# generator_cd4047_trafo_ct.net
KiCad netlist of a schematic drawn in EAGLE
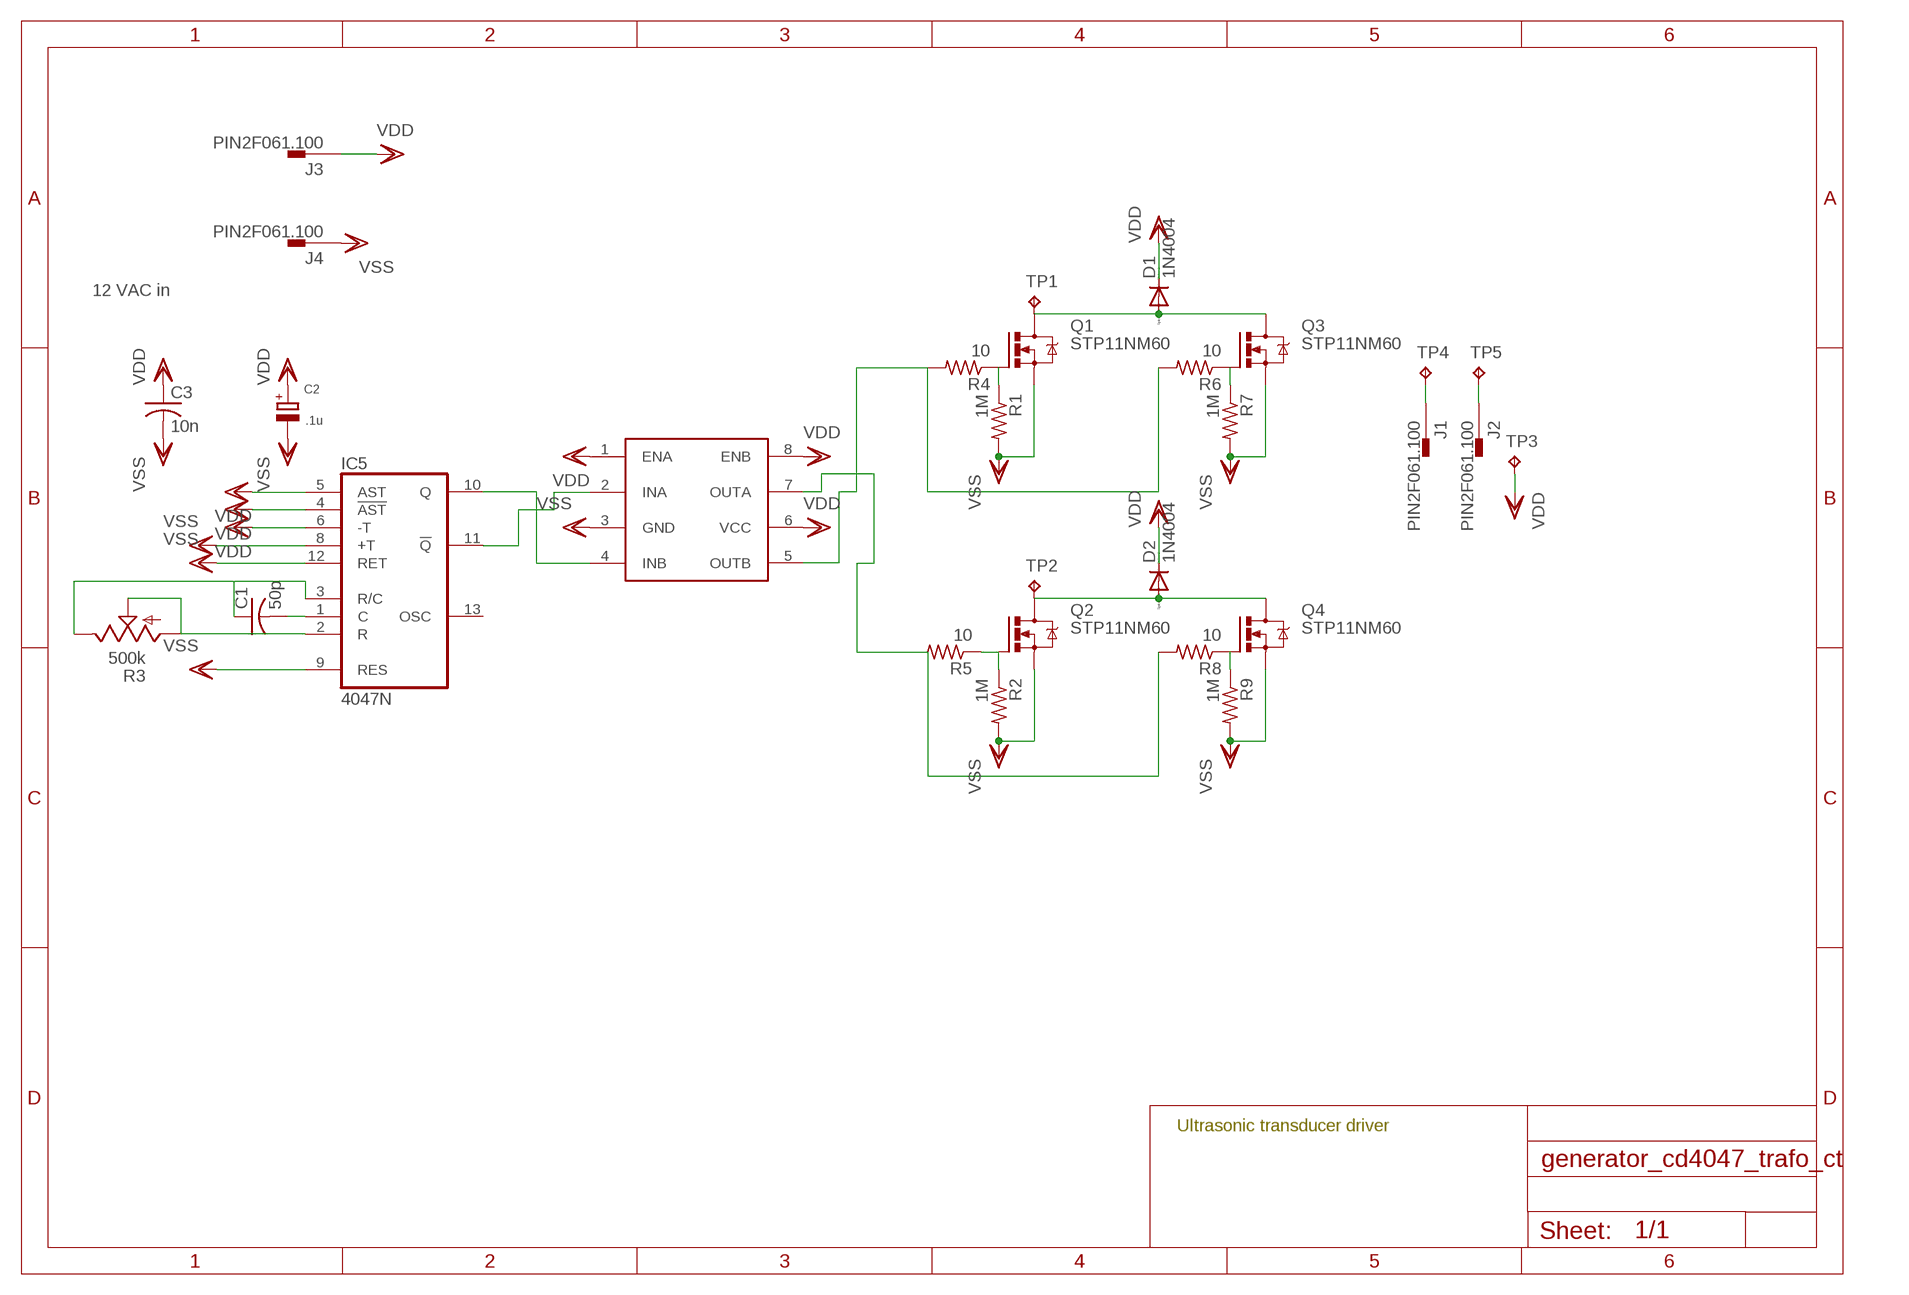
[diagram p0: schematic, sheet 1]

(export (version "E")
  (design (tool "Eeschema 10.0.6"))
  (components
    (comp (ref "C1")
      (value "50p")
      (footprint "eagle-import:C075-042X103")
      (libsource (lib "eagle-import") (part "C-US075-042X103"))
    )
    (comp (ref "C2")
      (value ".1u")
      (footprint "eagle-import:E5-8,5")
      (libsource (lib "eagle-import") (part "CPOL-EUE5-8.5"))
    )
    (comp (ref "C3")
      (value "10n")
      (footprint "eagle-import:C075-042X103")
      (libsource (lib "eagle-import") (part "C-US075-042X103"))
    )
    (comp (ref "D1")
      (value "1N4004")
      (footprint "eagle-import:DO41-10")
      (libsource (lib "eagle-import") (part "1N4004"))
    )
    (comp (ref "D2")
      (value "1N4004")
      (footprint "eagle-import:DO41-10")
      (libsource (lib "eagle-import") (part "1N4004"))
    )
    (comp (ref "IC5")
      (value "4047N")
      (footprint "eagle-import:DIL14")
      (libsource (lib "eagle-import") (part "4047N"))
    )
    (comp (ref "J1")
      (value "PIN2F061.100")
      (footprint "eagle-import:F061.100")
      (libsource (lib "eagle-import") (part "PIN2F061.100"))
    )
    (comp (ref "J2")
      (value "PIN2F061.100")
      (footprint "eagle-import:F061.100")
      (libsource (lib "eagle-import") (part "PIN2F061.100"))
    )
    (comp (ref "J3")
      (value "PIN2F061.100")
      (footprint "eagle-import:F061.100")
      (libsource (lib "eagle-import") (part "PIN2F061.100"))
    )
    (comp (ref "J4")
      (value "PIN2F061.100")
      (footprint "eagle-import:F061.100")
      (libsource (lib "eagle-import") (part "PIN2F061.100"))
    )
    (comp (ref "Q1")
      (value "STP11NM60")
      (footprint "eagle-import:TO220BV")
      (libsource (lib "eagle-import") (part "IRF530"))
    )
    (comp (ref "Q2")
      (value "STP11NM60")
      (footprint "eagle-import:TO220BV")
      (libsource (lib "eagle-import") (part "IRF530"))
    )
    (comp (ref "Q3")
      (value "STP11NM60")
      (footprint "eagle-import:TO220BV")
      (libsource (lib "eagle-import") (part "IRF530"))
    )
    (comp (ref "Q4")
      (value "STP11NM60")
      (footprint "eagle-import:TO220BV")
      (libsource (lib "eagle-import") (part "IRF530"))
    )
    (comp (ref "R1")
      (value "1M")
      (footprint "eagle-import:0207_10")
      (libsource (lib "eagle-import") (part "R-US_0207/10"))
    )
    (comp (ref "R2")
      (value "1M")
      (footprint "eagle-import:0207_10")
      (libsource (lib "eagle-import") (part "R-US_0207/10"))
    )
    (comp (ref "R3")
      (value "500k")
      (footprint "eagle-import:RJ9W")
      (libsource (lib "eagle-import") (part "TRIM_US-RJ9W"))
    )
    (comp (ref "R4")
      (value "10")
      (footprint "eagle-import:0207_10")
      (libsource (lib "eagle-import") (part "R-US_0207/10"))
    )
    (comp (ref "R5")
      (value "10")
      (footprint "eagle-import:0207_10")
      (libsource (lib "eagle-import") (part "R-US_0207/10"))
    )
    (comp (ref "R6")
      (value "10")
      (footprint "eagle-import:0207_10")
      (libsource (lib "eagle-import") (part "R-US_0207/10"))
    )
    (comp (ref "R7")
      (value "1M")
      (footprint "eagle-import:0207_10")
      (libsource (lib "eagle-import") (part "R-US_0207/10"))
    )
    (comp (ref "R8")
      (value "10")
      (footprint "eagle-import:0207_10")
      (libsource (lib "eagle-import") (part "R-US_0207/10"))
    )
    (comp (ref "R9")
      (value "1M")
      (footprint "eagle-import:0207_10")
      (libsource (lib "eagle-import") (part "R-US_0207/10"))
    )
    (comp (ref "TP1")
      (value "TPPAD1-20Y")
      (footprint "eagle-import:P1-20Y")
      (libsource (lib "eagle-import") (part "TPPAD1-20Y"))
    )
    (comp (ref "TP2")
      (value "TPPAD1-20Y")
      (footprint "eagle-import:P1-20Y")
      (libsource (lib "eagle-import") (part "TPPAD1-20Y"))
    )
    (comp (ref "TP3")
      (value "TPPAD1-20Y")
      (footprint "eagle-import:P1-20Y")
      (libsource (lib "eagle-import") (part "TPPAD1-20Y"))
    )
    (comp (ref "TP4")
      (value "TPPAD1-13Y")
      (footprint "eagle-import:P1-13Y")
      (libsource (lib "eagle-import") (part "TPPAD1-13Y"))
    )
    (comp (ref "TP5")
      (value "TPPAD1-13Y")
      (footprint "eagle-import:P1-13Y")
      (libsource (lib "eagle-import") (part "TPPAD1-13Y"))
    )
    (comp (ref "U$1")
      (value "UCC27425")
      (footprint "eagle-import:DIL08")
      (libsource (lib "eagle-import") (part "UCC27425"))
    )
  )
  (nets
    (net (code "1") (name "/N$6") (class "Default")
      (node (ref "D2") (pin "A") (pinfunction "A_A") (pintype "passive"))
      (node (ref "Q2") (pin "D") (pinfunction "D_D") (pintype "passive"))
      (node (ref "Q4") (pin "D") (pinfunction "D_D") (pintype "passive"))
      (node (ref "TP2") (pin "TP") (pinfunction "TP_TP") (pintype "input"))
    )
    (net (code "2") (name "Net-(D1-PadA)") (class "Default")
      (node (ref "D1") (pin "A") (pinfunction "A_A") (pintype "passive"))
      (node (ref "Q1") (pin "D") (pinfunction "D_D") (pintype "passive"))
      (node (ref "Q3") (pin "D") (pinfunction "D_D") (pintype "passive"))
      (node (ref "TP1") (pin "TP") (pinfunction "TP_TP") (pintype "input"))
    )
    (net (code "3") (name "Net-(IC5A-C)") (class "Default")
      (node (ref "C1") (pin "2") (pinfunction "2_2") (pintype "passive"))
      (node (ref "IC5") (pin "1") (pinfunction "C_1") (pintype "input"))
    )
    (net (code "4") (name "Net-(IC5A-Q)") (class "Default")
      (node (ref "IC5") (pin "10") (pinfunction "Q_10") (pintype "output"))
      (node (ref "U$1") (pin "4") (pinfunction "INB_4") (pintype "bidirectional"))
    )
    (net (code "5") (name "Net-(IC5A-R)") (class "Default")
      (node (ref "IC5") (pin "2") (pinfunction "R_2") (pintype "input"))
      (node (ref "R3") (pin "A") (pinfunction "A_A") (pintype "passive"))
      (node (ref "R3") (pin "S") (pinfunction "S_S") (pintype "passive"))
    )
    (net (code "6") (name "Net-(IC5A-R{slash}C)") (class "Default")
      (node (ref "C1") (pin "1") (pinfunction "1_1") (pintype "passive"))
      (node (ref "IC5") (pin "3") (pinfunction "R/C_3") (pintype "input"))
      (node (ref "R3") (pin "E") (pinfunction "E_E") (pintype "passive"))
    )
    (net (code "7") (name "Net-(IC5A-~{Q})") (class "Default")
      (node (ref "IC5") (pin "11") (pinfunction "~{Q}_11") (pintype "output"))
      (node (ref "U$1") (pin "2") (pinfunction "INA_2") (pintype "bidirectional"))
    )
    (net (code "8") (name "Net-(J1-1-PadA1)") (class "Default")
      (node (ref "J1") (pin "A1") (pinfunction "1_A1") (pintype "passive"))
      (node (ref "J1") (pin "A2") (pinfunction "1_A2") (pintype "passive"))
      (node (ref "TP4") (pin "TP") (pinfunction "TP_TP") (pintype "input"))
    )
    (net (code "9") (name "Net-(J2-1-PadA1)") (class "Default")
      (node (ref "J2") (pin "A1") (pinfunction "1_A1") (pintype "passive"))
      (node (ref "J2") (pin "A2") (pinfunction "1_A2") (pintype "passive"))
      (node (ref "TP5") (pin "TP") (pinfunction "TP_TP") (pintype "input"))
    )
    (net (code "10") (name "Net-(Q1-PadG)") (class "Default")
      (node (ref "Q1") (pin "G") (pinfunction "G_G") (pintype "passive"))
      (node (ref "R1") (pin "1") (pinfunction "1_1") (pintype "passive"))
      (node (ref "R4") (pin "1") (pinfunction "1_1") (pintype "passive"))
    )
    (net (code "11") (name "Net-(Q2-PadG)") (class "Default")
      (node (ref "Q2") (pin "G") (pinfunction "G_G") (pintype "passive"))
      (node (ref "R2") (pin "1") (pinfunction "1_1") (pintype "passive"))
      (node (ref "R5") (pin "1") (pinfunction "1_1") (pintype "passive"))
    )
    (net (code "12") (name "Net-(Q3-PadG)") (class "Default")
      (node (ref "Q3") (pin "G") (pinfunction "G_G") (pintype "passive"))
      (node (ref "R6") (pin "1") (pinfunction "1_1") (pintype "passive"))
      (node (ref "R7") (pin "1") (pinfunction "1_1") (pintype "passive"))
    )
    (net (code "13") (name "Net-(Q4-PadG)") (class "Default")
      (node (ref "Q4") (pin "G") (pinfunction "G_G") (pintype "passive"))
      (node (ref "R8") (pin "1") (pinfunction "1_1") (pintype "passive"))
      (node (ref "R9") (pin "1") (pinfunction "1_1") (pintype "passive"))
    )
    (net (code "14") (name "Net-(U$1-OUTA)") (class "Default")
      (node (ref "R5") (pin "2") (pinfunction "2_2") (pintype "passive"))
      (node (ref "R8") (pin "2") (pinfunction "2_2") (pintype "passive"))
      (node (ref "U$1") (pin "7") (pinfunction "OUTA_7") (pintype "bidirectional"))
    )
    (net (code "15") (name "Net-(U$1-OUTB)") (class "Default")
      (node (ref "R4") (pin "2") (pinfunction "2_2") (pintype "passive"))
      (node (ref "R6") (pin "2") (pinfunction "2_2") (pintype "passive"))
      (node (ref "U$1") (pin "5") (pinfunction "OUTB_5") (pintype "bidirectional"))
    )
    (net (code "16") (name "VDD") (class "Default")
      (node (ref "C2") (pin "+") (pinfunction "+_+") (pintype "passive"))
      (node (ref "C3") (pin "1") (pinfunction "1_1") (pintype "passive"))
      (node (ref "D1") (pin "C") (pinfunction "C_C") (pintype "passive"))
      (node (ref "D2") (pin "C") (pinfunction "C_C") (pintype "passive"))
      (node (ref "IC5") (pin "4") (pinfunction "~{AST}_4") (pintype "input"))
      (node (ref "IC5") (pin "5") (pinfunction "AST_5") (pintype "input"))
      (node (ref "IC5") (pin "6") (pinfunction "-T_6") (pintype "input"))
      (node (ref "J3") (pin "A1") (pinfunction "1_A1") (pintype "passive"))
      (node (ref "J3") (pin "A2") (pinfunction "1_A2") (pintype "passive"))
      (node (ref "TP3") (pin "TP") (pinfunction "TP_TP") (pintype "input"))
      (node (ref "U$1") (pin "1") (pinfunction "ENA_1") (pintype "bidirectional"))
      (node (ref "U$1") (pin "6") (pinfunction "VCC_6") (pintype "bidirectional"))
      (node (ref "U$1") (pin "8") (pinfunction "ENB_8") (pintype "bidirectional"))
    )
    (net (code "17") (name "VSS") (class "Default")
      (node (ref "C2") (pin "-") (pinfunction "-_-") (pintype "passive"))
      (node (ref "C3") (pin "2") (pinfunction "2_2") (pintype "passive"))
      (node (ref "IC5") (pin "12") (pinfunction "RET_12") (pintype "input"))
      (node (ref "IC5") (pin "8") (pinfunction "+T_8") (pintype "input"))
      (node (ref "IC5") (pin "9") (pinfunction "RES_9") (pintype "input"))
      (node (ref "J4") (pin "A1") (pinfunction "1_A1") (pintype "passive"))
      (node (ref "J4") (pin "A2") (pinfunction "1_A2") (pintype "passive"))
      (node (ref "Q1") (pin "S") (pinfunction "S_S") (pintype "passive"))
      (node (ref "Q2") (pin "S") (pinfunction "S_S") (pintype "passive"))
      (node (ref "Q3") (pin "S") (pinfunction "S_S") (pintype "passive"))
      (node (ref "Q4") (pin "S") (pinfunction "S_S") (pintype "passive"))
      (node (ref "R1") (pin "2") (pinfunction "2_2") (pintype "passive"))
      (node (ref "R2") (pin "2") (pinfunction "2_2") (pintype "passive"))
      (node (ref "R7") (pin "2") (pinfunction "2_2") (pintype "passive"))
      (node (ref "R9") (pin "2") (pinfunction "2_2") (pintype "passive"))
      (node (ref "U$1") (pin "3") (pinfunction "GND_3") (pintype "bidirectional"))
    )
    (net (code "18") (name "unconnected-(IC5A-OSC-Pad13)") (class "Default")
      (node (ref "IC5") (pin "13") (pinfunction "OSC_13") (pintype "output"))
    )
  )
)
